# YA-S-Blocks-V1_0.net
KiCad netlist of a schematic drawn in Altium Designer
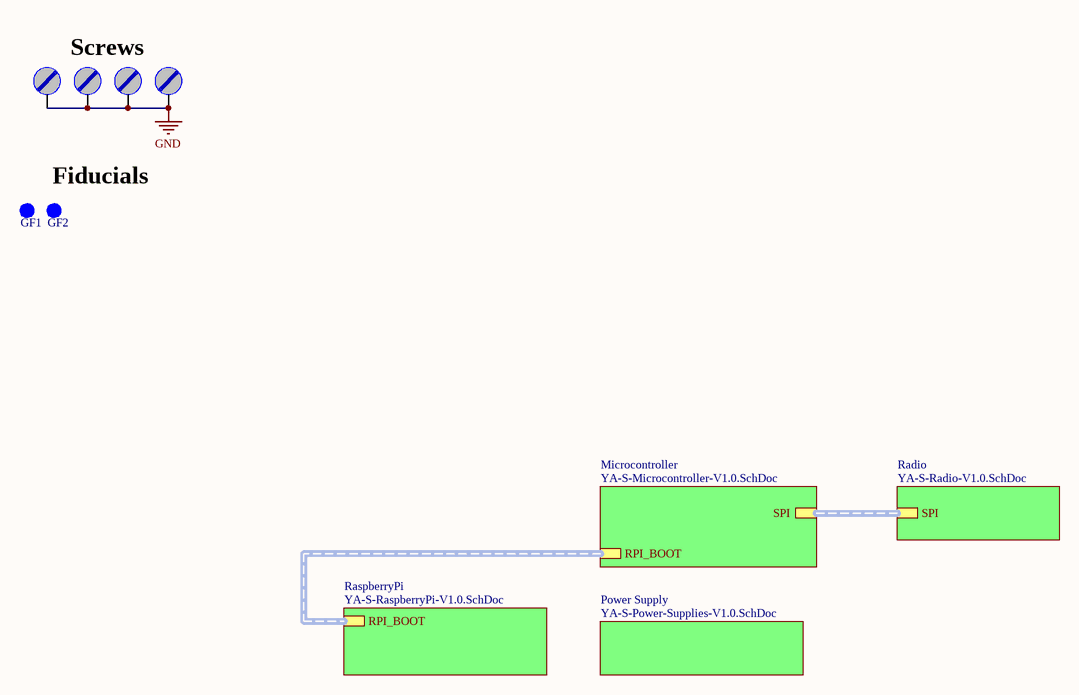
[diagram p0: YA-S-Blocks-V1.0.SchDoc]

(export (version "E")
  (design (tool "Eeschema 10.0.6"))
  (components
    (comp (ref "GF1")
      (value "Fiducial")
      (footprint "FIDUCIAL 1mm")
      (description "Guia Fiducial")
      (libsource (lib "Tecnoclade") (part "Fiducial"))
    )
    (comp (ref "GF2")
      (value "Fiducial")
      (footprint "FIDUCIAL 1mm")
      (description "Guia Fiducial")
      (libsource (lib "Tecnoclade") (part "Fiducial"))
    )
    (comp (ref "M1")
      (value "Furo de Fixação")
      (footprint "Furo_M3")
      (description "Furo para parafuso")
      (libsource (lib "Tecnoclade") (part "Parafuso"))
    )
    (comp (ref "M2")
      (value "Furo de Fixação")
      (footprint "Furo_M3")
      (description "Furo para parafuso")
      (libsource (lib "Tecnoclade") (part "Parafuso"))
    )
    (comp (ref "M3")
      (value "Furo de Fixação")
      (footprint "Furo_M3")
      (description "Furo para parafuso")
      (libsource (lib "Tecnoclade") (part "Parafuso"))
    )
    (comp (ref "M4")
      (value "Furo de Fixação")
      (footprint "Furo_M3")
      (description "Furo para parafuso")
      (libsource (lib "Tecnoclade") (part "Parafuso"))
    )
  )
  (nets
    (net (code "3") (name "GND") (class "Default")
      (node (ref "M1") (pin "X") (pinfunction "X_X") (pintype "passive"))
      (node (ref "M2") (pin "X") (pinfunction "X_X") (pintype "passive"))
      (node (ref "M3") (pin "X") (pinfunction "X_X") (pintype "passive"))
      (node (ref "M4") (pin "X") (pinfunction "X_X") (pintype "passive"))
    )
  )
)
